# Sheet1.net
KiCad netlist of a schematic drawn in Altium Designer
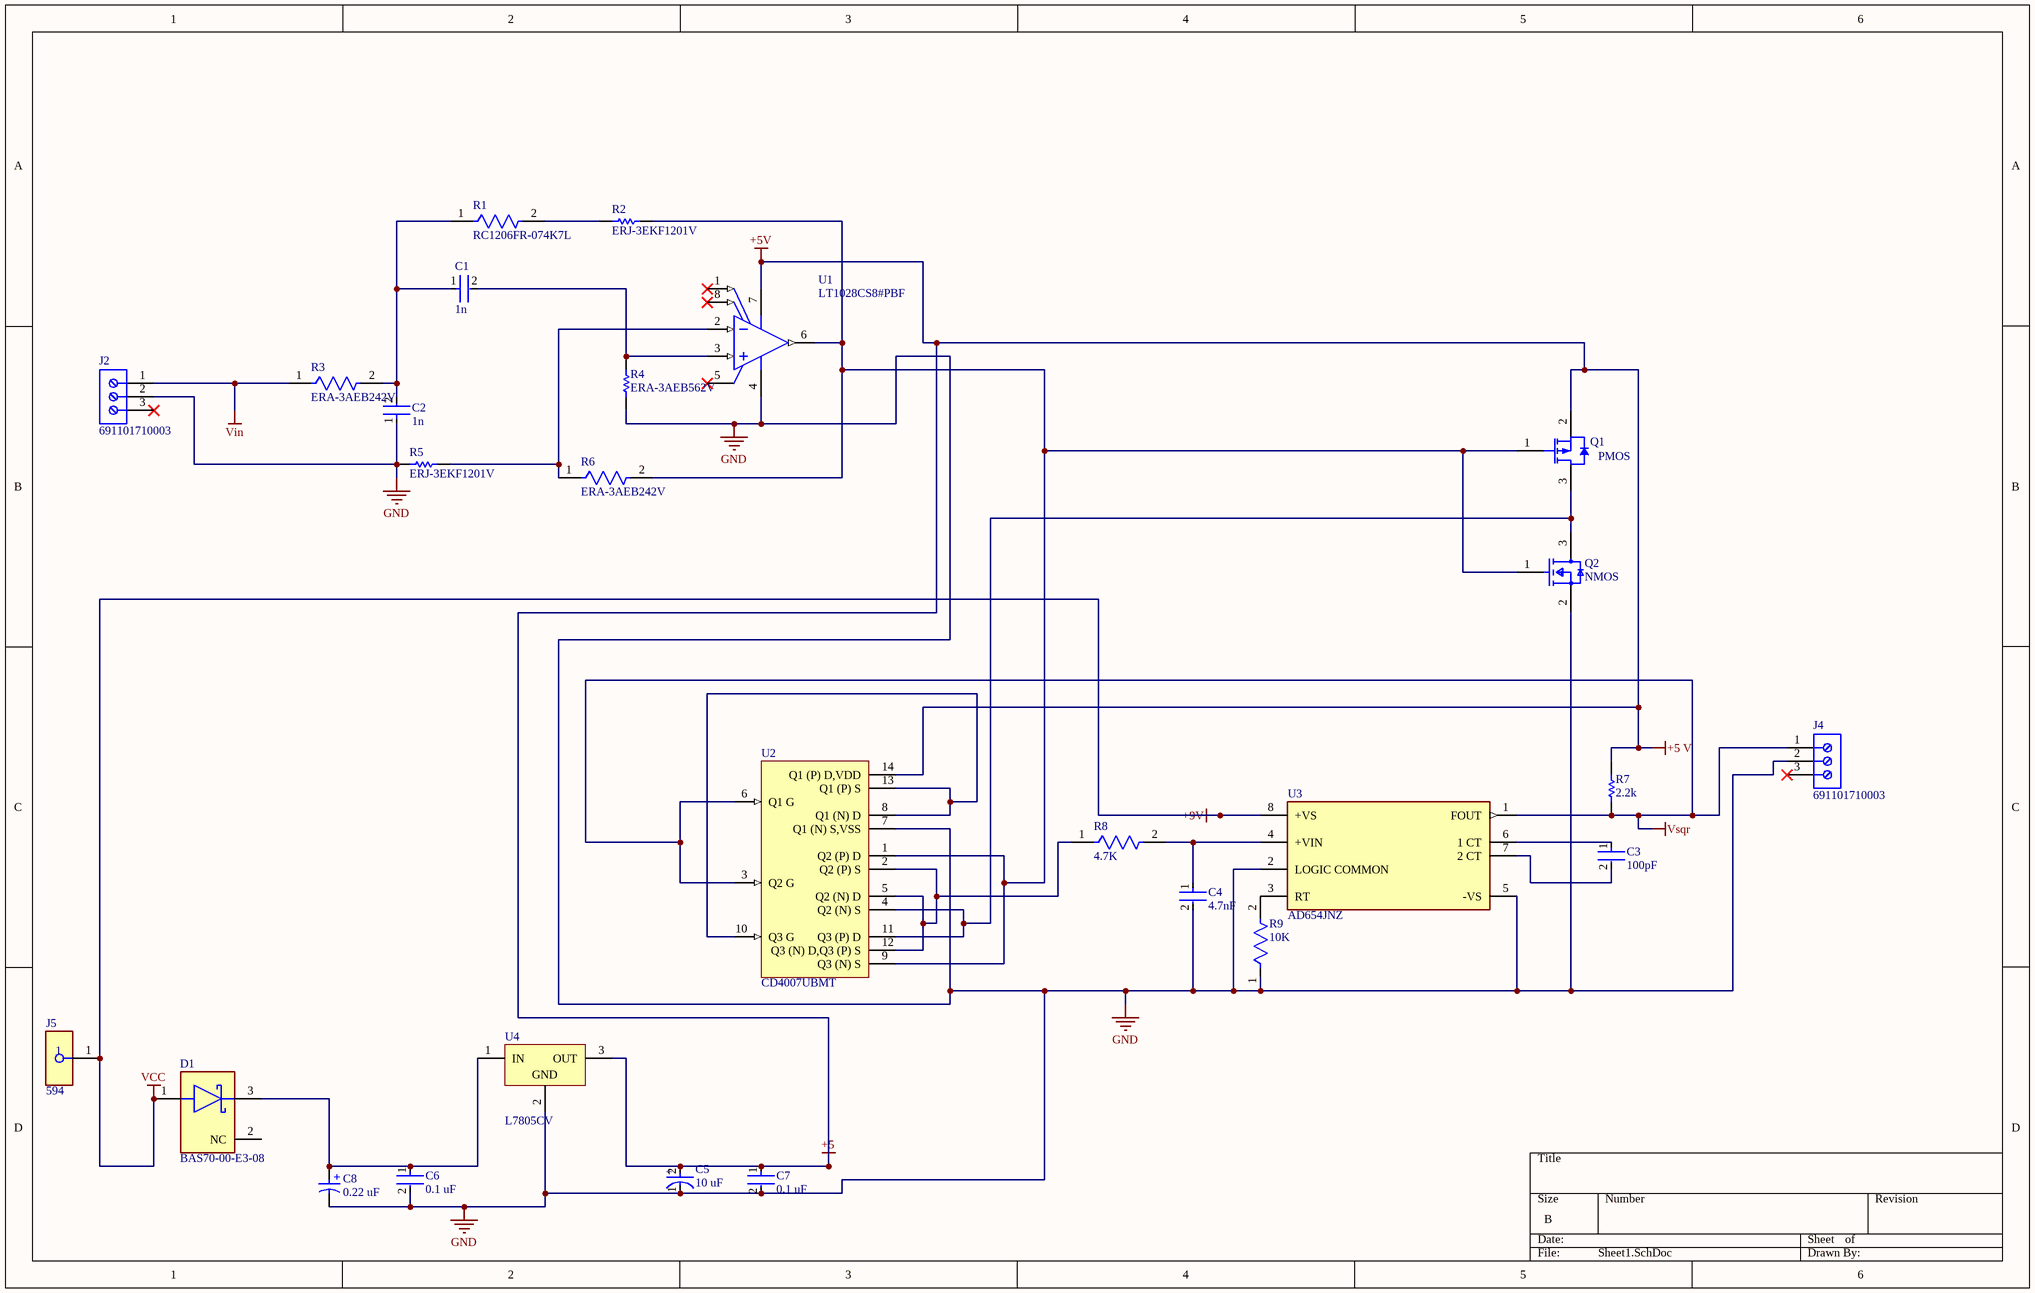
[diagram p0: Sheet1.SchDoc]

(export (version "E")
  (design (tool "Eeschema 10.0.6"))
  (components
    (comp (ref "C1")
      (value "1n")
      (footprint "FP-0603-L_1_6_0_15-W_0_81-IPC_A")
      (description "General Purpose Ceramic Capacitor, 0603, 1nF, 10%, X7R, 15%, 50V")
      (fields (field (name "VOLTAGE") "50V") (field (name "TOLERANCE") "10%"))
      (libsource (lib "Altium Content Vault") (part "02cd4be3c70576c341d710602a673aa"))
    )
    (comp (ref "C2")
      (value "1n")
      (footprint "FP-0603-L_1_6_0_15-W_0_81-IPC_A")
      (description "General Purpose Ceramic Capacitor, 0603, 1nF, 10%, X7R, 15%, 50V")
      (fields (field (name "VOLTAGE") "50V") (field (name "TOLERANCE") "10%"))
      (libsource (lib "Altium Content Vault") (part "02cd4be3c70576c341d710602a673aa"))
    )
    (comp (ref "C3")
      (value "100pF")
      (footprint "FP-C0402-BB-MFG")
      (description "CAP CER 100PF 50V 10% NP0 0402")
      (fields (field (name "TOLERANCE") "0.1") (field (name "MANUFACTURER PART NUMBER") "C0402C101K5GACTU"))
      (libsource (lib "Altium Content Vault") (part "b4654b650e69147ec39a6b967a45e02"))
    )
    (comp (ref "C4")
      (value "4.7nF")
      (footprint "FP-1206-L_3_2_0_2-W_1_6_0-IPC_B")
      (description "General Purpose Ceramic Capacitor, 1206, 4.7nF, 10%, X7R, 15%, 100V")
      (fields (field (name "VOLTAGE") "100V") (field (name "TOLERANCE") "10%"))
      (libsource (lib "Altium Content Vault") (part "02cd4be3c70576c341d710602a673aa"))
    )
    (comp (ref "C5")
      (value "10 uF")
      (footprint "FP-RAD-TH-D_5_0_5-L_11_1-MFG")
      (description "Aluminum Electrolytic Capacitors (Radial Lead Type) 10uF ±20% 50V")
      (fields (field (name "TOLERANCE") "20%") (field (name "VOLTAGE") "50V"))
      (libsource (lib "Altium Content Vault") (part "a00bbbee19879c290e62620ae7e47b1"))
    )
    (comp (ref "C6")
      (value "0.1 uF")
      (footprint "FP-RDE0P1-MFG")
      (description "Ceramic Capacitor 100nF ±10% 25V X7R Radial")
      (fields (field (name "TOLERANCE") "10%"))
      (libsource (lib "Altium Content Vault") (part "b4654b650e69147ec39a6b967a45e02"))
    )
    (comp (ref "C7")
      (value "0.1 uF")
      (footprint "FP-RDE0P1-MFG")
      (description "Ceramic Capacitor 100nF ±10% 25V X7R Radial")
      (fields (field (name "TOLERANCE") "10%"))
      (libsource (lib "Altium Content Vault") (part "b4654b650e69147ec39a6b967a45e02"))
    )
    (comp (ref "C8")
      (value "0.22 uF")
      (footprint "WCAP-ATG8_D5H11")
      (description "860010772002 WCAP-ATG8 Aluminum Electrolytic Capacitors")
      (fields (field (name "TOLERANCE") "20%"))
      (libsource (lib "Altium Content Vault") (part "Capacitor_Polarized"))
    )
    (comp (ref "D1")
      (value "BAS70-00-E3-08")
      (footprint "FP-6_541-5014_01-4-MFG")
      (description "DIODE SCHOTTKY 70V 200MA SOT23")
      (fields
        (field (name "MANUFACTURER") "Vishay")
        (field (name "OCTOPART") "https://octopart.com/bas70-00-e3-08-vishay-30324832")
      )
      (libsource (lib "Altium Content Vault") (part "1b5d8b3549dd4c20f048bc998ce9ad4"))
    )
    (comp (ref "J2")
      (value "691101710003")
      (footprint "691101710003")
      (fields (field (name "VOLTAGE") "250V"))
      (libsource (lib "Altium Content Vault") (part "TBL - 1R - 03P - Screw"))
    )
    (comp (ref "J4")
      (value "691101710003")
      (footprint "691101710003")
      (fields (field (name "VOLTAGE") "250V"))
      (libsource (lib "Altium Content Vault") (part "TBL - 1R - 03P - Screw"))
    )
    (comp (ref "J5")
      (value "594")
      (footprint "FP-594-MFG")
      (description "BATTERY CONTACT SNAP 9V PC PIN")
      (libsource (lib "Altium Content Vault") (part "c5c826e0c4b67fe3b42ef77f2d4decc"))
    )
    (comp (ref "Q1")
      (value "PMOS")
      (footprint "INF-SOT23_L")
      (description "SIPMOS(R) Small-Signal-Transistor, -0.33 A, 2 Ohm, -60 V, 3-Pin SOT-23, RoHS, Tape and Reel")
      (fields (field (name "MANUFACTURER") "Infineon"))
      (libsource (lib "Altium Content Vault") (part "PEMOS-GSD-3"))
    )
    (comp (ref "Q2")
      (value "NMOS")
      (footprint "FP-318-08-IPC_B")
      (description "MOSFET N-CH 50V 220MA SOT-23")
      (libsource (lib "Altium Content Vault") (part "3b9c635fedb024a5347a57b145af9cc"))
    )
    (comp (ref "R1")
      (value "RC1206FR-074K7L")
      (footprint "FP-RC1206-0_65-IPC_B")
      (description "RES SMD 4.7K OHM 1% 1/4W 1206")
      (fields (field (name "TOLERANCE") "1%"))
      (libsource (lib "Altium Content Vault") (part "1029c3af85768c4190bb7ad29bc67b5"))
    )
    (comp (ref "R2")
      (value "ERJ-3EKF1201V")
      (footprint "RESC1609X55X30ML15T15")
      (description "Chip Resistor, 1.2 KOhm, +/- 1%, 0.1 W, -55 to 155 degC, 0603 (1608 Metric), RoHS, Tape and Reel")
      (fields (field (name "MANUFACTURER") "Panasonic") (field (name "TOLERANCE") "1%"))
      (libsource (lib "Altium Content Vault") (part "RES-2"))
    )
    (comp (ref "R3")
      (value "ERA-3AEB242V")
      (footprint "FP-ERA3A-MFG")
      (fields (field (name "TOLERANCE") "0.1%"))
      (libsource (lib "Altium Content Vault") (part "1029c3af85768c4190bb7ad29bc67b5"))
    )
    (comp (ref "R4")
      (value "ERA-3AEB562V")
      (footprint "RESC1608X55X30NL20T20")
      (fields (field (name "MANUFACTURER") "Panasonic"))
      (libsource (lib "Altium Content Vault") (part "RES"))
    )
    (comp (ref "R5")
      (value "ERJ-3EKF1201V")
      (footprint "RESC1609X55X30ML15T15")
      (description "Chip Resistor, 1.2 KOhm, +/- 1%, 0.1 W, -55 to 155 degC, 0603 (1608 Metric), RoHS, Tape and Reel")
      (fields (field (name "MANUFACTURER") "Panasonic") (field (name "TOLERANCE") "1%"))
      (libsource (lib "Altium Content Vault") (part "RES-2"))
    )
    (comp (ref "R6")
      (value "ERA-3AEB242V")
      (footprint "FP-ERA3A-MFG")
      (fields (field (name "TOLERANCE") "0.1%"))
      (libsource (lib "Altium Content Vault") (part "1029c3af85768c4190bb7ad29bc67b5"))
    )
    (comp (ref "R7")
      (value "2.2k")
      (footprint "RESC1608X55X25LL10T15")
      (fields (field (name "TOLERANCE") "1%") (field (name "MANUFACTURER") "Yageo"))
      (libsource (lib "Altium Content Vault") (part "RES-2"))
    )
    (comp (ref "R8")
      (value "4.7K")
      (footprint "FP-CRCW0402-e3-IPC_A")
      (description "RES Thick Film, 4.7kΩ, 5%, 0.063W, 200ppm/°C, 0402")
      (fields (field (name "TOLERANCE") "5%"))
      (libsource (lib "Altium Content Vault") (part "1029c3af85768c4190bb7ad29bc67b5"))
    )
    (comp (ref "R9")
      (value "10K")
      (footprint "FP-ERA3A-IPC_C")
      (description "RES SMD 10K OHM 0.1% 1/10W 0603")
      (fields (field (name "TOLERANCE") "0.1%"))
      (libsource (lib "Altium Content Vault") (part "4e5f8b3dd332802e91518312df5df73"))
    )
    (comp (ref "U1")
      (value "LT1028CS8#PBF")
      (footprint "LT-S8-8_M")
      (fields
        (field (name "LINEAR TECHNOLOGY PART NUMBER") "LT1028")
        (field (name "MANUFACTURER") "Linear Technology")
      )
      (libsource (lib "Altium Content Vault") (part "LT-LT1028-8"))
    )
    (comp (ref "U2")
      (value "CD4007UBMT")
      (footprint "D0014A_N")
      (description "CMOS Dual Complementary Pair Plus Inverter, D0014A, SMALL T&R")
      (fields
        (field (name "MANUFACTURER") "Texas Instruments")
        (field (name "GENERIC PART NUMBER") "CD4007UB")
      )
      (libsource (lib "Altium Content Vault") (part "TI-CD4007UB-14"))
    )
    (comp (ref "U3")
      (value "AD654JNZ")
      (footprint "FP-N-8-MFG")
      (description "IC V/F CONV 500KHZ 8DIP")
      (libsource (lib "Altium Content Vault") (part "402f73415fd159cf69bfe20f2e05010"))
    )
    (comp (ref "U4")
      (value "L7805CV")
      (footprint "TO220")
      (description "Positive Voltage Regulator, 5V, 3-Pin TO-220")
      (libsource (lib "Altium Content Vault") (part "PM-REG-L4940-SIL3"))
    )
  )
  (nets
    (net (code "1") (name "+5") (class "Default")
      (node (ref "C5") (pin "2") (pinfunction "A_2") (pintype "passive"))
      (node (ref "C7") (pin "1") (pinfunction "1_1") (pintype "passive"))
      (node (ref "Q1") (pin "2") (pinfunction "SOURCE_2") (pintype "passive"))
      (node (ref "R7") (pin "2") (pinfunction "2_2") (pintype "passive"))
      (node (ref "U1") (pin "7") (pinfunction "V+_7") (pintype "power_in"))
      (node (ref "U2") (pin "14") (pinfunction "Q1_(P)_D,VDD_14") (pintype "passive"))
      (node (ref "U4") (pin "3") (pinfunction "OUT_3") (pintype "power_in"))
    )
    (net (code "2") (name "+9V") (class "Default")
      (node (ref "D1") (pin "1") (pinfunction "A_1") (pintype "passive"))
      (node (ref "J5") (pin "1") (pinfunction "1_1") (pintype "passive"))
      (node (ref "U3") (pin "8") (pinfunction "+VS_8") (pintype "power_in"))
    )
    (net (code "3") (name "GND") (class "Default")
      (node (ref "C2") (pin "1") (pinfunction "1_1") (pintype "passive"))
      (node (ref "C4") (pin "2") (pinfunction "2_2") (pintype "passive"))
      (node (ref "C5") (pin "1") (pinfunction "C_1") (pintype "passive"))
      (node (ref "C6") (pin "2") (pinfunction "2_2") (pintype "passive"))
      (node (ref "C7") (pin "2") (pinfunction "2_2") (pintype "passive"))
      (node (ref "C8") (pin "2") (pinfunction "N_2") (pintype "passive"))
      (node (ref "J2") (pin "2") (pinfunction "2_2") (pintype "passive"))
      (node (ref "J4") (pin "2") (pinfunction "2_2") (pintype "passive"))
      (node (ref "Q2") (pin "2") (pinfunction "S_2") (pintype "passive"))
      (node (ref "R4") (pin "1") (pinfunction "1_1") (pintype "passive"))
      (node (ref "R5") (pin "1") (pinfunction "1_1") (pintype "passive"))
      (node (ref "R9") (pin "1") (pinfunction "1_1") (pintype "passive"))
      (node (ref "U1") (pin "4") (pinfunction "V-_4") (pintype "power_in"))
      (node (ref "U2") (pin "7") (pinfunction "Q1_(N)_S,VSS_7") (pintype "passive"))
      (node (ref "U3") (pin "2") (pinfunction "LOGIC_COMMON_2") (pintype "passive"))
      (node (ref "U3") (pin "5") (pinfunction "-VS_5") (pintype "power_in"))
      (node (ref "U4") (pin "2") (pinfunction "GND_2") (pintype "power_in"))
    )
    (net (code "4") (name "Net-(C1-Pad1)") (class "Default")
      (node (ref "C1") (pin "1") (pinfunction "1_1") (pintype "passive"))
      (node (ref "C2") (pin "2") (pinfunction "2_2") (pintype "passive"))
      (node (ref "R1") (pin "1") (pinfunction "1_1") (pintype "passive"))
      (node (ref "R3") (pin "2") (pinfunction "2_2") (pintype "passive"))
    )
    (net (code "5") (name "Net-(C8-P)") (class "Default")
      (node (ref "C6") (pin "1") (pinfunction "1_1") (pintype "passive"))
      (node (ref "C8") (pin "1") (pinfunction "P_1") (pintype "passive"))
      (node (ref "D1") (pin "3") (pinfunction "C_3") (pintype "passive"))
      (node (ref "U4") (pin "1") (pinfunction "IN_1") (pintype "power_in"))
    )
    (net (code "6") (name "Net-(Q1-DRAIN)") (class "Default")
      (node (ref "Q1") (pin "3") (pinfunction "DRAIN_3") (pintype "passive"))
      (node (ref "Q2") (pin "3") (pinfunction "D_3") (pintype "passive"))
      (node (ref "U2") (pin "11") (pinfunction "Q3_(P)_D_11") (pintype "open_collector"))
      (node (ref "U2") (pin "4") (pinfunction "Q2_(N)_S_4") (pintype "open_emitter"))
    )
    (net (code "7") (name "Net-(Q1-GATE)") (class "Default")
      (node (ref "Q1") (pin "1") (pinfunction "GATE_1") (pintype "passive"))
      (node (ref "Q2") (pin "1") (pinfunction "G_1") (pintype "passive"))
      (node (ref "R2") (pin "2") (pinfunction "2_2") (pintype "passive"))
      (node (ref "R6") (pin "2") (pinfunction "2_2") (pintype "passive"))
      (node (ref "U1") (pin "6") (pinfunction "OUT_6") (pintype "output"))
      (node (ref "U2") (pin "1") (pinfunction "Q2_(P)_D_1") (pintype "open_collector"))
      (node (ref "U2") (pin "9") (pinfunction "Q3_(N)_S_9") (pintype "open_emitter"))
    )
    (net (code "8") (name "Net-(R1-Pad2)") (class "Default")
      (node (ref "R1") (pin "2") (pinfunction "2_2") (pintype "passive"))
      (node (ref "R2") (pin "1") (pinfunction "1_1") (pintype "passive"))
    )
    (net (code "9") (name "Net-(U1-+IN)") (class "Default")
      (node (ref "C1") (pin "2") (pinfunction "2_2") (pintype "passive"))
      (node (ref "R4") (pin "2") (pinfunction "2_2") (pintype "passive"))
      (node (ref "U1") (pin "3") (pinfunction "+IN_3") (pintype "input"))
    )
    (net (code "10") (name "Net-(U1--IN)") (class "Default")
      (node (ref "R5") (pin "2") (pinfunction "2_2") (pintype "passive"))
      (node (ref "R6") (pin "1") (pinfunction "1_1") (pintype "passive"))
      (node (ref "U1") (pin "2") (pinfunction "-IN_2") (pintype "input"))
    )
    (net (code "11") (name "Net-(U2-Q1_(N)_D)") (class "Default")
      (node (ref "U2") (pin "10") (pinfunction "Q3_G_10") (pintype "input"))
      (node (ref "U2") (pin "13") (pinfunction "Q1_(P)_S_13") (pintype "open_emitter"))
      (node (ref "U2") (pin "8") (pinfunction "Q1_(N)_D_8") (pintype "open_collector"))
    )
    (net (code "12") (name "Net-(U2-Q2_(N)_D)") (class "Default")
      (node (ref "R8") (pin "1") (pinfunction "1_1") (pintype "passive"))
      (node (ref "U2") (pin "12") (pinfunction "Q3_(N)_D,Q3_(P)_S_12") (pintype "passive"))
      (node (ref "U2") (pin "2") (pinfunction "Q2_(P)_S_2") (pintype "open_emitter"))
      (node (ref "U2") (pin "5") (pinfunction "Q2_(N)_D_5") (pintype "open_collector"))
    )
    (net (code "13") (name "Net-(U3-+VIN)") (class "Default")
      (node (ref "C4") (pin "1") (pinfunction "1_1") (pintype "passive"))
      (node (ref "R8") (pin "2") (pinfunction "2_2") (pintype "passive"))
      (node (ref "U3") (pin "4") (pinfunction "+VIN_4") (pintype "power_in"))
    )
    (net (code "14") (name "Net-(U3-1_CT)") (class "Default")
      (node (ref "C3") (pin "1") (pinfunction "1_1") (pintype "passive"))
      (node (ref "U3") (pin "6") (pinfunction "1_CT_6") (pintype "passive"))
    )
    (net (code "15") (name "Net-(U3-2_CT)") (class "Default")
      (node (ref "C3") (pin "2") (pinfunction "2_2") (pintype "passive"))
      (node (ref "U3") (pin "7") (pinfunction "2_CT_7") (pintype "passive"))
    )
    (net (code "16") (name "Net-(U3-RT)") (class "Default")
      (node (ref "R9") (pin "2") (pinfunction "2_2") (pintype "passive"))
      (node (ref "U3") (pin "3") (pinfunction "RT_3") (pintype "passive"))
    )
    (net (code "17") (name "Vin") (class "Default")
      (node (ref "J2") (pin "1") (pinfunction "1_1") (pintype "passive"))
      (node (ref "R3") (pin "1") (pinfunction "1_1") (pintype "passive"))
    )
    (net (code "18") (name "Vsqr") (class "Default")
      (node (ref "J4") (pin "1") (pinfunction "1_1") (pintype "passive"))
      (node (ref "R7") (pin "1") (pinfunction "1_1") (pintype "passive"))
      (node (ref "U2") (pin "3") (pinfunction "Q2_G_3") (pintype "input"))
      (node (ref "U2") (pin "6") (pinfunction "Q1_G_6") (pintype "input"))
      (node (ref "U3") (pin "1") (pinfunction "FOUT_1") (pintype "output"))
    )
    (net (code "19") (name "unconnected-(D1-NC-Pad2)") (class "Default")
      (node (ref "D1") (pin "2") (pinfunction "NC_2") (pintype "passive"))
    )
    (net (code "20") (name "unconnected-(J2-Pad3)") (class "Default")
      (node (ref "J2") (pin "3") (pinfunction "3_3") (pintype "passive+no_connect"))
    )
    (net (code "21") (name "unconnected-(J4-Pad3)") (class "Default")
      (node (ref "J4") (pin "3") (pinfunction "3_3") (pintype "passive+no_connect"))
    )
    (net (code "22") (name "unconnected-(U1-OVERCOMP-Pad5)") (class "Default")
      (node (ref "U1") (pin "5") (pinfunction "OVERCOMP_5") (pintype "passive+no_connect"))
    )
    (net (code "23") (name "unconnected-(U1-VOS_TRIM-Pad1)") (class "Default")
      (node (ref "U1") (pin "1") (pinfunction "VOS_TRIM_1") (pintype "input+no_connect"))
    )
    (net (code "24") (name "unconnected-(U1-VOS_TRIM-Pad8)") (class "Default")
      (node (ref "U1") (pin "8") (pinfunction "VOS_TRIM_8") (pintype "input+no_connect"))
    )
  )
)
